# open-weller-pen.net
KiCad netlist of a schematic drawn in Altium Designer
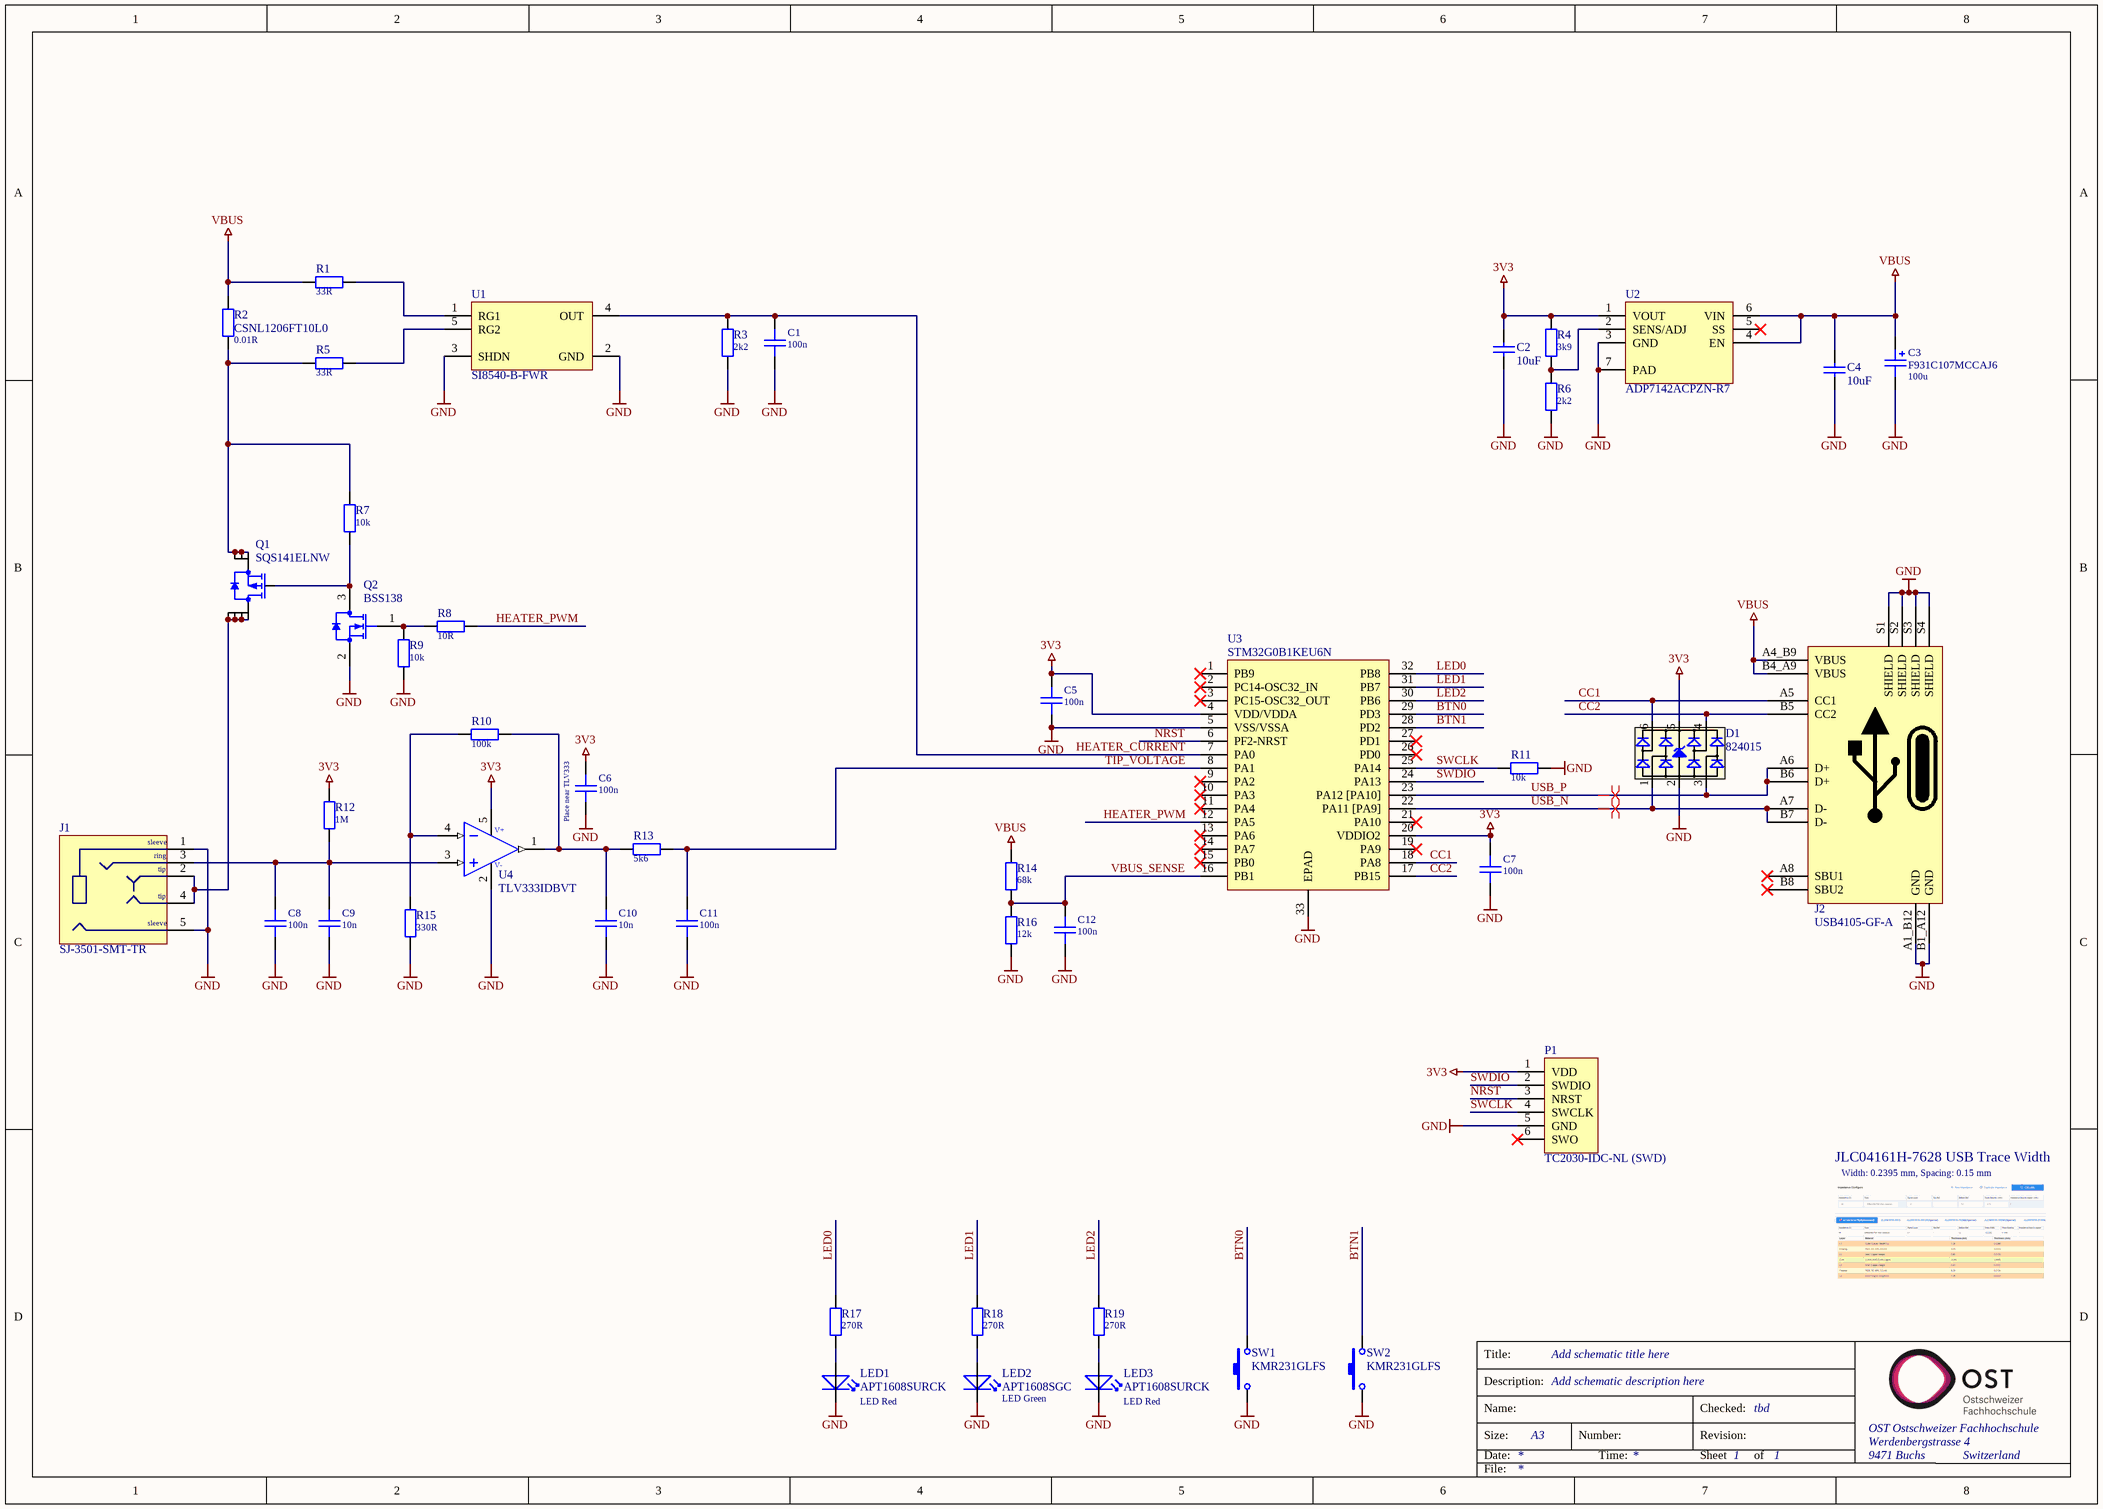
[diagram p0: open-weller-pen.SchDoc]

(export (version "E")
  (design (tool "Eeschema 10.0.6"))
  (components
    (comp (ref "C1")
      (value "100n")
      (footprint "Generic_Cap0603_2_R")
      (description "100n, X7R, 10%, 50V, 0603")
      (fields (field (name "MANUFACTURER") "Kyocera AVX") (field (name "Comment") "06035C104kAT2A"))
      (libsource (lib "OST Vault") (part "Capacitor"))
    )
    (comp (ref "C2")
      (value "GRM188R61E106KA73D")
      (footprint "Generic_Cap0603_2_RW")
      (description "10uF, X5R, 10%, 25V")
      (fields (field (name "MANUFACTURER") "Murata") (field (name "SHORTDESCRIPTION") "10uF"))
      (libsource (lib "OST Vault") (part "Generic_Capacitor_2"))
    )
    (comp (ref "C3")
      (value "F931C107MCCAJ6")
      (footprint "Generic_CPOL_C-2312_1P_2N_2")
      (description "100u, TANTAL, 20%, 16V, C(2312)")
      (fields (field (name "ALTIUM_VALUE") "100u") (field (name "MANUFACTURER") "AVX"))
      (libsource (lib "OST Vault") (part "Polarized Capacitor"))
    )
    (comp (ref "C4")
      (value "GRM188R61E106KA73D")
      (footprint "Generic_Cap0603_2_RW")
      (description "10uF, X5R, 10%, 25V")
      (fields (field (name "MANUFACTURER") "Murata") (field (name "SHORTDESCRIPTION") "10uF"))
      (libsource (lib "OST Vault") (part "Generic_Capacitor_2"))
    )
    (comp (ref "C5")
      (value "100n")
      (footprint "Generic_Cap0603_2_R")
      (description "100n, X7R, 10%, 50V, 0603")
      (fields (field (name "MANUFACTURER") "Kyocera AVX") (field (name "Comment") "06035C104kAT2A"))
      (libsource (lib "OST Vault") (part "Capacitor"))
    )
    (comp (ref "C6")
      (value "100n")
      (footprint "Generic_Cap0603_2_R")
      (description "100n, X7R, 10%, 50V, 0603")
      (fields (field (name "MANUFACTURER") "Kyocera AVX") (field (name "Comment") "06035C104kAT2A"))
      (libsource (lib "OST Vault") (part "Capacitor"))
    )
    (comp (ref "C7")
      (value "100n")
      (footprint "Generic_Cap0603_2_R")
      (description "100n, X7R, 10%, 50V, 0603")
      (fields (field (name "MANUFACTURER") "Kyocera AVX") (field (name "Comment") "06035C104kAT2A"))
      (libsource (lib "OST Vault") (part "Capacitor"))
    )
    (comp (ref "C8")
      (value "100n")
      (footprint "Generic_Cap0603_2_R")
      (description "100n, X7R, 10%, 50V, 0603")
      (fields (field (name "MANUFACTURER") "Kyocera AVX") (field (name "Comment") "06035C104kAT2A"))
      (libsource (lib "OST Vault") (part "Capacitor"))
    )
    (comp (ref "C9")
      (value "10n")
      (footprint "Generic_Cap0603_2_R")
      (description "10n, X7R, 10%, 50V, 0603")
      (fields (field (name "MANUFACTURER") "Kyocera AVX") (field (name "Comment") "06035C103kAT2A"))
      (libsource (lib "OST Vault") (part "Capacitor"))
    )
    (comp (ref "C10")
      (value "10n")
      (footprint "Generic_Cap0603_2_R")
      (description "10n, X7R, 10%, 50V, 0603")
      (fields (field (name "MANUFACTURER") "Kyocera AVX") (field (name "Comment") "06035C103kAT2A"))
      (libsource (lib "OST Vault") (part "Capacitor"))
    )
    (comp (ref "C11")
      (value "100n")
      (footprint "Generic_Cap0603_2_R")
      (description "100n, X7R, 10%, 50V, 0603")
      (fields (field (name "MANUFACTURER") "Kyocera AVX") (field (name "Comment") "06035C104kAT2A"))
      (libsource (lib "OST Vault") (part "Capacitor"))
    )
    (comp (ref "C12")
      (value "100n")
      (footprint "Generic_Cap0603_2_R")
      (description "100n, X7R, 10%, 50V, 0603")
      (fields (field (name "MANUFACTURER") "Kyocera AVX") (field (name "Comment") "06035C104kAT2A"))
      (libsource (lib "OST Vault") (part "Capacitor"))
    )
    (comp (ref "D1")
      (value "824015")
      (footprint "GENERIC_SOT23-6_6_R")
      (description "TVS Diode Array, 5V, Unidirectional")
      (fields (field (name "MANUFACTURER") "Wurth"))
      (libsource (lib "OST Vault") (part "WE_824015_SOT23-6L_6"))
    )
    (comp (ref "J1")
      (value "SJ-3501-SMT-TR")
      (footprint "CUI_SJ-3501-SMT-TR_5")
      (description "Audio Jack, 3.5mm, Mid Mount")
      (fields (field (name "MANUFACTURER") "CUI"))
      (libsource (lib "OST Vault") (part "CUI_SJ-3501-SMT-TR_5"))
    )
    (comp (ref "J2")
      (value "USB4105-GF-A")
      (footprint "GCT_USB4105-GF-A_16_R")
      (description "USB Type C, Edge Mount, USB 2.0")
      (fields (field (name "MANUFACTURER") "GCT"))
      (libsource (lib "OST Vault") (part "GCT_USB4105-GF-A_16"))
    )
    (comp (ref "LED1")
      (value "APT1608SURCK")
      (footprint "Kingbright_1608_2_RW")
      (description "LED Red")
      (fields (field (name "MANUFACTURER") "Kingbright") (field (name "SHORTDESCRIPTION") "LED Red"))
      (libsource (lib "OST Vault") (part "Generic_LED_1K2A_2"))
    )
    (comp (ref "LED2")
      (value "APT1608SGC")
      (footprint "Kingbright_1608_2_RW")
      (description "LED Green")
      (fields (field (name "MANUFACTURER") "Kingbright") (field (name "SHORTDESCRIPTION") "LED Green"))
      (libsource (lib "OST Vault") (part "Generic_LED_1K2A_2"))
    )
    (comp (ref "LED3")
      (value "APT1608SURCK")
      (footprint "Kingbright_1608_2_RW")
      (description "LED Red")
      (fields (field (name "MANUFACTURER") "Kingbright") (field (name "SHORTDESCRIPTION") "LED Red"))
      (libsource (lib "OST Vault") (part "Generic_LED_1K2A_2"))
    )
    (comp (ref "P1")
      (value "TC2030-IDC-NL (SWD)")
      (footprint "TagConnectLLC_TC2030_6")
      (description "TagConnect TC2030-IDC-NL footprint for SWD debugger.")
      (fields (field (name "MANUFACTURER") "TagConnectLLC"))
      (libsource (lib "OST Vault") (part "TagConnectLLC_TC2030_6"))
    )
    (comp (ref "Q1")
      (value "SQS141ELNW")
      (footprint "Vishay_PowerPAK_1212-8_8")
      (description "MOSFET, P-Ch, 40V, 100A")
      (fields (field (name "MANUFACTURER") "Vishay"))
      (libsource (lib "OST Vault") (part "Vishay_SQS141ELNW_PowerPAK_1212-8SLW_8"))
    )
    (comp (ref "Q2")
      (value "BSS138")
      (footprint "Generic_SOT23_3_RWH")
      (description "MOSFET, N-Ch, 50V, 220mA")
      (fields (field (name "MANUFACTURER") "ON"))
      (libsource (lib "OST Vault") (part "MOSFET, N-Channel"))
    )
    (comp (ref "R1")
      (value "33R")
      (footprint "Generic_Res0603_2_RW")
      (description "33R, 1%, 0.1W, 0603")
      (fields (field (name "MANUFACTURER") "YAGEO") (field (name "Comment") "RC0603FR-0733RL"))
      (libsource (lib "") (part "Resistor_2"))
    )
    (comp (ref "R2")
      (value "CSNL1206FT10L0")
      (footprint "Generic_Res1206_2_RW")
      (description "0.01R, Shunt, 1W, 1%, 1206")
      (fields (field (name "ALTIUM_VALUE") "0.01R") (field (name "MANUFACTURER") "Stackpole Electronics Inc"))
      (libsource (lib "OST Vault") (part "Resistor"))
    )
    (comp (ref "R3")
      (value "2k2")
      (footprint "Generic_Res0603_2_RW")
      (description "2k2, 1%, 0.1W, 0603")
      (fields (field (name "MANUFACTURER") "YAGEO") (field (name "Comment") "RC0603FR-072K2L"))
      (libsource (lib "OST Vault") (part "Resistor"))
    )
    (comp (ref "R4")
      (value "3k9")
      (footprint "Generic_Res0603_2_RW")
      (description "3k9, 1%, 0.1W, 0603")
      (fields (field (name "MANUFACTURER") "YAGEO") (field (name "Comment") "RC0603FR-073K9L"))
      (libsource (lib "OST Vault") (part "Resistor"))
    )
    (comp (ref "R5")
      (value "33R")
      (footprint "Generic_Res0603_2_RW")
      (description "33R, 1%, 0.1W, 0603")
      (fields (field (name "MANUFACTURER") "YAGEO") (field (name "Comment") "RC0603FR-0733RL"))
      (libsource (lib "") (part "Resistor_2"))
    )
    (comp (ref "R6")
      (value "2k2")
      (footprint "Generic_Res0603_2_RW")
      (description "2k2, 1%, 0.1W, 0603")
      (fields (field (name "MANUFACTURER") "YAGEO") (field (name "Comment") "RC0603FR-072K2L"))
      (libsource (lib "OST Vault") (part "Resistor"))
    )
    (comp (ref "R7")
      (value "10k")
      (footprint "Generic_Res0603_2_RW")
      (description "10k, 1%, 0.1W, 0603")
      (fields (field (name "MANUFACTURER") "YAGEO") (field (name "Comment") "RC0603FR-0710KL"))
      (libsource (lib "OST Vault") (part "Resistor"))
    )
    (comp (ref "R8")
      (value "10R")
      (footprint "Generic_Res0603_2_RW")
      (description "10R, 1%, 0.1W, 0603")
      (fields (field (name "MANUFACTURER") "YAGEO") (field (name "Comment") "RC0603FR-0710RL"))
      (libsource (lib "") (part "Resistor_2"))
    )
    (comp (ref "R9")
      (value "10k")
      (footprint "Generic_Res0603_2_RW")
      (description "10k, 1%, 0.1W, 0603")
      (fields (field (name "MANUFACTURER") "YAGEO") (field (name "Comment") "RC0603FR-0710KL"))
      (libsource (lib "OST Vault") (part "Resistor"))
    )
    (comp (ref "R10")
      (value "100k")
      (footprint "Generic_Res0603_2_RW")
      (description "100k, 1%, 0.1W, 0603")
      (fields (field (name "MANUFACTURER") "YAGEO") (field (name "Comment") "RC0603FR-07100KL"))
      (libsource (lib "") (part "Resistor_1"))
    )
    (comp (ref "R11")
      (value "10k")
      (footprint "Generic_Res0603_2_RW")
      (description "10k, 1%, 0.1W, 0603")
      (fields (field (name "MANUFACTURER") "YAGEO") (field (name "Comment") "RC0603FR-0710KL"))
      (libsource (lib "") (part "Resistor_1"))
    )
    (comp (ref "R12")
      (value "1M")
      (footprint "Generic_Res0603_2_RW")
      (description "1M, 1%, 0.1W, 0603")
      (fields (field (name "MANUFACTURER") "YAGEO") (field (name "Comment") "RC0603FR-071ML"))
      (libsource (lib "OST Vault") (part "Resistor"))
    )
    (comp (ref "R13")
      (value "5k6")
      (footprint "Generic_Res0603_2_RW")
      (description "5k6, 1%, 0.1W, 0603")
      (fields (field (name "MANUFACTURER") "YAGEO") (field (name "Comment") "RC0603FR-075K6L"))
      (libsource (lib "") (part "Resistor_2"))
    )
    (comp (ref "R14")
      (value "68k")
      (footprint "Generic_Res0603_2_RW")
      (description "68k, 1%, 0.1W, 0603")
      (fields (field (name "MANUFACTURER") "YAGEO") (field (name "Comment") "RC0603FR-0768KL"))
      (libsource (lib "OST Vault") (part "Resistor"))
    )
    (comp (ref "R15")
      (value "330R")
      (footprint "Generic_Res0603_2_RW")
      (description "330R, 1%, 0.1W, 0603")
      (fields (field (name "MANUFACTURER") "YAGEO") (field (name "Comment") "RC0603FR-07330RL"))
      (libsource (lib "") (part "Resistor_3"))
    )
    (comp (ref "R16")
      (value "12k")
      (footprint "Generic_Res0603_2_RW")
      (description "12k, 1%, 0.1W, 0603")
      (fields (field (name "MANUFACTURER") "YAGEO") (field (name "Comment") "RC0603FR-0712KL"))
      (libsource (lib "OST Vault") (part "Resistor"))
    )
    (comp (ref "R17")
      (value "270R")
      (footprint "Generic_Res0603_2_RW")
      (description "270R, 1%, 0.1W, 0603")
      (fields (field (name "MANUFACTURER") "YAGEO") (field (name "Comment") "RC0603FR-07270RL"))
      (libsource (lib "OST Vault") (part "Resistor"))
    )
    (comp (ref "R18")
      (value "270R")
      (footprint "Generic_Res0603_2_RW")
      (description "270R, 1%, 0.1W, 0603")
      (fields (field (name "MANUFACTURER") "YAGEO") (field (name "Comment") "RC0603FR-07270RL"))
      (libsource (lib "OST Vault") (part "Resistor"))
    )
    (comp (ref "R19")
      (value "270R")
      (footprint "Generic_Res0603_2_RW")
      (description "270R, 1%, 0.1W, 0603")
      (fields (field (name "MANUFACTURER") "YAGEO") (field (name "Comment") "RC0603FR-07270RL"))
      (libsource (lib "OST Vault") (part "Resistor"))
    )
    (comp (ref "SW1")
      (value "KMR231GLFS")
      (footprint "CK_KMR231GLFS_4")
      (description "Tactile Switch, Thin Type")
      (fields (field (name "MANUFACTURER") "CK"))
      (libsource (lib "OST Vault") (part "SW_2"))
    )
    (comp (ref "SW2")
      (value "KMR231GLFS")
      (footprint "CK_KMR231GLFS_4")
      (description "Tactile Switch, Thin Type")
      (fields (field (name "MANUFACTURER") "CK"))
      (libsource (lib "OST Vault") (part "SW_2"))
    )
    (comp (ref "U1")
      (value "SI8540-B-FWR")
      (footprint "GENERIC_SOT23-5_5_R")
      (description "High-side Current Sense Amplifier")
      (fields (field (name "MANUFACTURER") "Skyworks"))
      (libsource (lib "OST Vault") (part "SKYWORKS_Si8540_SOT23-5_5"))
    )
    (comp (ref "U2")
      (value "ADP7142ACPZN-R7")
      (footprint "ANALOG_LFCSP6_7_R")
      (description "40 V, 200 mA, Low Noise, ADJ CMOS LDO Linear Regulator")
      (fields (field (name "MANUFACTURER") "Analog"))
      (libsource (lib "OST Vault") (part "ANALOG_ADP7142_LFCSP6_7"))
    )
    (comp (ref "U3")
      (value "STM32G0B1KEU6N")
      (footprint "ST_UFQFPN32_33_R")
      (description "Arm Cortex-M0+ 32-bit MCU up to 512KB Flash 144KB RAM, USB-PD")
      (fields (field (name "MANUFACTURER") "ST"))
      (libsource (lib "OST Vault") (part "ST_STM32G0B1KxUxN_UFQFPN32_33"))
    )
    (comp (ref "U4")
      (value "TLV333IDBVT")
      (footprint "TI_SOT23_5_RH")
      (description "350kHz GBW, Low Noise, Zero Drift, 5.5V")
      (fields (field (name "MANUFACTURER") "TI"))
      (libsource (lib "OST Vault") (part "TI_OPV_SOT23_5"))
    )
  )
  (nets
    (net (code "1") (name "/BTN0") (class "Default")
      (node (ref "SW1") (pin "2") (pinfunction "2_2") (pintype "passive"))
      (node (ref "U3") (pin "29") (pinfunction "PD3_29") (pintype "passive"))
    )
    (net (code "2") (name "/BTN1") (class "Default")
      (node (ref "SW2") (pin "2") (pinfunction "2_2") (pintype "passive"))
      (node (ref "U3") (pin "28") (pinfunction "PD2_28") (pintype "passive"))
    )
    (net (code "3") (name "/CC1") (class "Default")
      (node (ref "D1") (pin "6") (pinfunction "I/O4_6") (pintype "passive"))
      (node (ref "J2") (pin "A5") (pinfunction "CC1_A5") (pintype "passive"))
      (node (ref "U3") (pin "18") (pinfunction "PA8_18") (pintype "passive"))
    )
    (net (code "4") (name "/CC2") (class "Default")
      (node (ref "D1") (pin "4") (pinfunction "I/O3_4") (pintype "passive"))
      (node (ref "J2") (pin "B5") (pinfunction "CC2_B5") (pintype "passive"))
      (node (ref "U3") (pin "17") (pinfunction "PB15_17") (pintype "passive"))
    )
    (net (code "5") (name "/HEATER_CURRENT") (class "Default")
      (node (ref "C1") (pin "2") (pinfunction "2_2") (pintype "passive"))
      (node (ref "R3") (pin "1") (pinfunction "1_1") (pintype "passive"))
      (node (ref "U1") (pin "4") (pinfunction "OUT_4") (pintype "passive"))
      (node (ref "U3") (pin "7") (pinfunction "PA0_7") (pintype "passive"))
    )
    (net (code "6") (name "/HEATER_PWM") (class "Default")
      (node (ref "R8") (pin "1") (pinfunction "1_1") (pintype "passive"))
      (node (ref "U3") (pin "12") (pinfunction "PA5_12") (pintype "passive"))
    )
    (net (code "7") (name "/LED0") (class "Default")
      (node (ref "R17") (pin "1") (pinfunction "1_1") (pintype "passive"))
      (node (ref "U3") (pin "32") (pinfunction "PB8_32") (pintype "passive"))
    )
    (net (code "8") (name "/LED1") (class "Default")
      (node (ref "R18") (pin "1") (pinfunction "1_1") (pintype "passive"))
      (node (ref "U3") (pin "31") (pinfunction "PB7_31") (pintype "passive"))
    )
    (net (code "9") (name "/LED2") (class "Default")
      (node (ref "R19") (pin "1") (pinfunction "1_1") (pintype "passive"))
      (node (ref "U3") (pin "30") (pinfunction "PB6_30") (pintype "passive"))
    )
    (net (code "10") (name "/NRST") (class "Default")
      (node (ref "P1") (pin "3") (pinfunction "NRST_3") (pintype "passive"))
      (node (ref "U3") (pin "6") (pinfunction "PF2-NRST_6") (pintype "passive"))
    )
    (net (code "11") (name "/SWCLK") (class "Default")
      (node (ref "P1") (pin "4") (pinfunction "SWCLK_4") (pintype "passive"))
      (node (ref "R11") (pin "1") (pinfunction "1_1") (pintype "passive"))
      (node (ref "U3") (pin "25") (pinfunction "PA14_25") (pintype "passive"))
    )
    (net (code "12") (name "/SWDIO") (class "Default")
      (node (ref "P1") (pin "2") (pinfunction "SWDIO_2") (pintype "passive"))
      (node (ref "U3") (pin "24") (pinfunction "PA13_24") (pintype "passive"))
    )
    (net (code "13") (name "/TIP_VOLTAGE") (class "Default")
      (node (ref "C11") (pin "2") (pinfunction "2_2") (pintype "passive"))
      (node (ref "R13") (pin "1") (pinfunction "1_1") (pintype "passive"))
      (node (ref "U3") (pin "8") (pinfunction "PA1_8") (pintype "passive"))
    )
    (net (code "14") (name "/USB_N") (class "Default")
      (node (ref "D1") (pin "1") (pinfunction "I/O1_1") (pintype "passive"))
      (node (ref "J2") (pin "A7") (pinfunction "D-_A7") (pintype "passive"))
      (node (ref "J2") (pin "B7") (pinfunction "D-_B7") (pintype "passive"))
      (node (ref "U3") (pin "22") (pinfunction "PA11_[PA9]_22") (pintype "passive"))
    )
    (net (code "15") (name "/USB_P") (class "Default")
      (node (ref "D1") (pin "3") (pinfunction "I/O2_3") (pintype "passive"))
      (node (ref "J2") (pin "A6") (pinfunction "D+_A6") (pintype "passive"))
      (node (ref "J2") (pin "B6") (pinfunction "D+_B6") (pintype "passive"))
      (node (ref "U3") (pin "23") (pinfunction "PA12_[PA10]_23") (pintype "passive"))
    )
    (net (code "16") (name "/VBUS_SENSE") (class "Default")
      (node (ref "C12") (pin "2") (pinfunction "2_2") (pintype "passive"))
      (node (ref "R14") (pin "2") (pinfunction "2_2") (pintype "passive"))
      (node (ref "R16") (pin "1") (pinfunction "1_1") (pintype "passive"))
      (node (ref "U3") (pin "16") (pinfunction "PB1_16") (pintype "passive"))
    )
    (net (code "17") (name "3V3") (class "Default")
      (node (ref "C2") (pin "2") (pinfunction "2_2") (pintype "passive"))
      (node (ref "C5") (pin "2") (pinfunction "2_2") (pintype "passive"))
      (node (ref "C6") (pin "2") (pinfunction "2_2") (pintype "passive"))
      (node (ref "C7") (pin "2") (pinfunction "2_2") (pintype "passive"))
      (node (ref "D1") (pin "5") (pinfunction "VDD_5") (pintype "passive"))
      (node (ref "P1") (pin "1") (pinfunction "VDD_1") (pintype "passive"))
      (node (ref "R12") (pin "1") (pinfunction "1_1") (pintype "passive"))
      (node (ref "R4") (pin "1") (pinfunction "1_1") (pintype "passive"))
      (node (ref "U2") (pin "1") (pinfunction "VOUT_1") (pintype "passive"))
      (node (ref "U3") (pin "20") (pinfunction "VDDIO2_20") (pintype "power_in"))
      (node (ref "U3") (pin "4") (pinfunction "VDD/VDDA_4") (pintype "power_in"))
      (node (ref "U4") (pin "5") (pinfunction "V+_5") (pintype "power_in"))
    )
    (net (code "18") (name "GND") (class "Default")
      (node (ref "C1") (pin "1") (pinfunction "1_1") (pintype "passive"))
      (node (ref "C10") (pin "1") (pinfunction "1_1") (pintype "passive"))
      (node (ref "C11") (pin "1") (pinfunction "1_1") (pintype "passive"))
      (node (ref "C12") (pin "1") (pinfunction "1_1") (pintype "passive"))
      (node (ref "C2") (pin "1") (pinfunction "1_1") (pintype "passive"))
      (node (ref "C3") (pin "2") (pinfunction "2_2") (pintype "passive"))
      (node (ref "C4") (pin "1") (pinfunction "1_1") (pintype "passive"))
      (node (ref "C5") (pin "1") (pinfunction "1_1") (pintype "passive"))
      (node (ref "C6") (pin "1") (pinfunction "1_1") (pintype "passive"))
      (node (ref "C7") (pin "1") (pinfunction "1_1") (pintype "passive"))
      (node (ref "C8") (pin "1") (pinfunction "1_1") (pintype "passive"))
      (node (ref "C9") (pin "1") (pinfunction "1_1") (pintype "passive"))
      (node (ref "D1") (pin "2") (pinfunction "GND_2") (pintype "passive"))
      (node (ref "J1") (pin "1") (pinfunction "sleeve_1") (pintype "passive"))
      (node (ref "J1") (pin "5") (pinfunction "sleeve_5") (pintype "passive"))
      (node (ref "J2") (pin "A1_B12") (pinfunction "GND_A1_B12") (pintype "power_in"))
      (node (ref "J2") (pin "B1_A12") (pinfunction "GND_B1_A12") (pintype "power_in"))
      (node (ref "J2") (pin "S1") (pinfunction "SHIELD_S1") (pintype "passive"))
      (node (ref "J2") (pin "S2") (pinfunction "SHIELD_S2") (pintype "passive"))
      (node (ref "J2") (pin "S3") (pinfunction "SHIELD_S3") (pintype "passive"))
      (node (ref "J2") (pin "S4") (pinfunction "SHIELD_S4") (pintype "passive"))
      (node (ref "LED1") (pin "1") (pinfunction "K_1") (pintype "passive"))
      (node (ref "LED2") (pin "1") (pinfunction "K_1") (pintype "passive"))
      (node (ref "LED3") (pin "1") (pinfunction "K_1") (pintype "passive"))
      (node (ref "P1") (pin "5") (pinfunction "GND_5") (pintype "passive"))
      (node (ref "Q2") (pin "2") (pinfunction "S_2") (pintype "passive"))
      (node (ref "R11") (pin "2") (pinfunction "2_2") (pintype "passive"))
      (node (ref "R15") (pin "1") (pinfunction "1_1") (pintype "passive"))
      (node (ref "R16") (pin "2") (pinfunction "2_2") (pintype "passive"))
      (node (ref "R3") (pin "2") (pinfunction "2_2") (pintype "passive"))
      (node (ref "R6") (pin "2") (pinfunction "2_2") (pintype "passive"))
      (node (ref "R9") (pin "2") (pinfunction "2_2") (pintype "passive"))
      (node (ref "SW1") (pin "1") (pinfunction "1_1") (pintype "passive"))
      (node (ref "SW2") (pin "1") (pinfunction "1_1") (pintype "passive"))
      (node (ref "U1") (pin "2") (pinfunction "GND_2") (pintype "power_in"))
      (node (ref "U1") (pin "3") (pinfunction "SHDN_3") (pintype "passive"))
      (node (ref "U2") (pin "3") (pinfunction "GND_3") (pintype "passive"))
      (node (ref "U2") (pin "7") (pinfunction "PAD_7") (pintype "passive"))
      (node (ref "U3") (pin "33") (pinfunction "EPAD_33") (pintype "power_in"))
      (node (ref "U3") (pin "5") (pinfunction "VSS/VSSA_5") (pintype "power_in"))
      (node (ref "U4") (pin "2") (pinfunction "V-_2") (pintype "power_in"))
    )
    (net (code "19") (name "Net-(J1-ring)") (class "Default")
      (node (ref "C8") (pin "2") (pinfunction "2_2") (pintype "passive"))
      (node (ref "C9") (pin "2") (pinfunction "2_2") (pintype "passive"))
      (node (ref "J1") (pin "3") (pinfunction "ring_3") (pintype "passive"))
      (node (ref "R12") (pin "2") (pinfunction "2_2") (pintype "passive"))
      (node (ref "U4") (pin "3") (pinfunction "IN+_3") (pintype "input"))
    )
    (net (code "20") (name "Net-(J1-tip-Pad2)") (class "Default")
      (node (ref "J1") (pin "2") (pinfunction "tip_2") (pintype "passive"))
      (node (ref "J1") (pin "4") (pinfunction "tip_4") (pintype "passive"))
      (node (ref "Q1") (pin "5") (pinfunction "D_5") (pintype "passive"))
      (node (ref "Q1") (pin "6") (pinfunction "D_6") (pintype "passive"))
      (node (ref "Q1") (pin "7") (pinfunction "D_7") (pintype "passive"))
      (node (ref "Q1") (pin "8") (pinfunction "D_8") (pintype "passive"))
    )
    (net (code "21") (name "Net-(LED1-A)") (class "Default")
      (node (ref "LED1") (pin "2") (pinfunction "A_2") (pintype "passive"))
      (node (ref "R17") (pin "2") (pinfunction "2_2") (pintype "passive"))
    )
    (net (code "22") (name "Net-(LED2-A)") (class "Default")
      (node (ref "LED2") (pin "2") (pinfunction "A_2") (pintype "passive"))
      (node (ref "R18") (pin "2") (pinfunction "2_2") (pintype "passive"))
    )
    (net (code "23") (name "Net-(LED3-A)") (class "Default")
      (node (ref "LED3") (pin "2") (pinfunction "A_2") (pintype "passive"))
      (node (ref "R19") (pin "2") (pinfunction "2_2") (pintype "passive"))
    )
    (net (code "24") (name "Net-(Q1-G)") (class "Default")
      (node (ref "Q1") (pin "4") (pinfunction "G_4") (pintype "passive"))
      (node (ref "Q2") (pin "3") (pinfunction "D_3") (pintype "passive"))
      (node (ref "R7") (pin "2") (pinfunction "2_2") (pintype "passive"))
    )
    (net (code "25") (name "Net-(Q1-S-Pad1)") (class "Default")
      (node (ref "Q1") (pin "1") (pinfunction "S_1") (pintype "passive"))
      (node (ref "Q1") (pin "2") (pinfunction "S_2") (pintype "passive"))
      (node (ref "Q1") (pin "3") (pinfunction "S_3") (pintype "passive"))
      (node (ref "R2") (pin "2") (pinfunction "2_2") (pintype "passive"))
      (node (ref "R5") (pin "2") (pinfunction "2_2") (pintype "passive"))
      (node (ref "R7") (pin "1") (pinfunction "1_1") (pintype "passive"))
    )
    (net (code "26") (name "Net-(Q2-G)") (class "Default")
      (node (ref "Q2") (pin "1") (pinfunction "G_1") (pintype "passive"))
      (node (ref "R8") (pin "2") (pinfunction "2_2") (pintype "passive"))
      (node (ref "R9") (pin "1") (pinfunction "1_1") (pintype "passive"))
    )
    (net (code "27") (name "Net-(U1-RG1)") (class "Default")
      (node (ref "R1") (pin "1") (pinfunction "1_1") (pintype "passive"))
      (node (ref "U1") (pin "1") (pinfunction "RG1_1") (pintype "passive"))
    )
    (net (code "28") (name "Net-(U1-RG2)") (class "Default")
      (node (ref "R5") (pin "1") (pinfunction "1_1") (pintype "passive"))
      (node (ref "U1") (pin "5") (pinfunction "RG2_5") (pintype "passive"))
    )
    (net (code "29") (name "Net-(U2-SENS{slash}ADJ)") (class "Default")
      (node (ref "R4") (pin "2") (pinfunction "2_2") (pintype "passive"))
      (node (ref "R6") (pin "1") (pinfunction "1_1") (pintype "passive"))
      (node (ref "U2") (pin "2") (pinfunction "SENS/ADJ_2") (pintype "passive"))
    )
    (net (code "30") (name "Net-(U4-IN-)") (class "Default")
      (node (ref "R10") (pin "1") (pinfunction "1_1") (pintype "passive"))
      (node (ref "R15") (pin "2") (pinfunction "2_2") (pintype "passive"))
      (node (ref "U4") (pin "4") (pinfunction "IN-_4") (pintype "input"))
    )
    (net (code "31") (name "Net-(U4-OUT)") (class "Default")
      (node (ref "C10") (pin "2") (pinfunction "2_2") (pintype "passive"))
      (node (ref "R10") (pin "2") (pinfunction "2_2") (pintype "passive"))
      (node (ref "R13") (pin "2") (pinfunction "2_2") (pintype "passive"))
      (node (ref "U4") (pin "1") (pinfunction "OUT_1") (pintype "output"))
    )
    (net (code "32") (name "VBUS") (class "Default")
      (node (ref "C3") (pin "1") (pinfunction "1_1") (pintype "passive"))
      (node (ref "C4") (pin "2") (pinfunction "2_2") (pintype "passive"))
      (node (ref "J2") (pin "A4_B9") (pinfunction "VBUS_A4_B9") (pintype "power_in"))
      (node (ref "J2") (pin "B4_A9") (pinfunction "VBUS_B4_A9") (pintype "power_in"))
      (node (ref "R1") (pin "2") (pinfunction "2_2") (pintype "passive"))
      (node (ref "R14") (pin "1") (pinfunction "1_1") (pintype "passive"))
      (node (ref "R2") (pin "1") (pinfunction "1_1") (pintype "passive"))
      (node (ref "U2") (pin "4") (pinfunction "EN_4") (pintype "passive"))
      (node (ref "U2") (pin "6") (pinfunction "VIN_6") (pintype "passive"))
    )
    (net (code "33") (name "unconnected-(J2-SBU1-PadA8)") (class "Default")
      (node (ref "J2") (pin "A8") (pinfunction "SBU1_A8") (pintype "passive+no_connect"))
    )
    (net (code "34") (name "unconnected-(J2-SBU2-PadB8)") (class "Default")
      (node (ref "J2") (pin "B8") (pinfunction "SBU2_B8") (pintype "passive+no_connect"))
    )
    (net (code "35") (name "unconnected-(P1-SWO-Pad6)") (class "Default")
      (node (ref "P1") (pin "6") (pinfunction "SWO_6") (pintype "passive+no_connect"))
    )
    (net (code "36") (name "unconnected-(U2-SS-Pad5)") (class "Default")
      (node (ref "U2") (pin "5") (pinfunction "SS_5") (pintype "passive+no_connect"))
    )
    (net (code "37") (name "unconnected-(U3-PA2-Pad9)") (class "Default")
      (node (ref "U3") (pin "9") (pinfunction "PA2_9") (pintype "passive+no_connect"))
    )
    (net (code "38") (name "unconnected-(U3-PA3-Pad10)") (class "Default")
      (node (ref "U3") (pin "10") (pinfunction "PA3_10") (pintype "passive+no_connect"))
    )
    (net (code "39") (name "unconnected-(U3-PA4-Pad11)") (class "Default")
      (node (ref "U3") (pin "11") (pinfunction "PA4_11") (pintype "passive+no_connect"))
    )
    (net (code "40") (name "unconnected-(U3-PA6-Pad13)") (class "Default")
      (node (ref "U3") (pin "13") (pinfunction "PA6_13") (pintype "passive+no_connect"))
    )
    (net (code "41") (name "unconnected-(U3-PA7-Pad14)") (class "Default")
      (node (ref "U3") (pin "14") (pinfunction "PA7_14") (pintype "passive+no_connect"))
    )
    (net (code "42") (name "unconnected-(U3-PA9-Pad19)") (class "Default")
      (node (ref "U3") (pin "19") (pinfunction "PA9_19") (pintype "passive+no_connect"))
    )
    (net (code "43") (name "unconnected-(U3-PA10-Pad21)") (class "Default")
      (node (ref "U3") (pin "21") (pinfunction "PA10_21") (pintype "passive+no_connect"))
    )
    (net (code "44") (name "unconnected-(U3-PB0-Pad15)") (class "Default")
      (node (ref "U3") (pin "15") (pinfunction "PB0_15") (pintype "passive+no_connect"))
    )
    (net (code "45") (name "unconnected-(U3-PB9-Pad1)") (class "Default")
      (node (ref "U3") (pin "1") (pinfunction "PB9_1") (pintype "passive+no_connect"))
    )
    (net (code "46") (name "unconnected-(U3-PC14-OSC32_IN-Pad2)") (class "Default")
      (node (ref "U3") (pin "2") (pinfunction "PC14-OSC32_IN_2") (pintype "passive+no_connect"))
    )
    (net (code "47") (name "unconnected-(U3-PC15-OSC32_OUT-Pad3)") (class "Default")
      (node (ref "U3") (pin "3") (pinfunction "PC15-OSC32_OUT_3") (pintype "passive+no_connect"))
    )
    (net (code "48") (name "unconnected-(U3-PD0-Pad26)") (class "Default")
      (node (ref "U3") (pin "26") (pinfunction "PD0_26") (pintype "passive+no_connect"))
    )
    (net (code "49") (name "unconnected-(U3-PD1-Pad27)") (class "Default")
      (node (ref "U3") (pin "27") (pinfunction "PD1_27") (pintype "passive+no_connect"))
    )
  )
)
